# brainslug_34drc.net
KiCad netlist of a schematic drawn in EAGLE
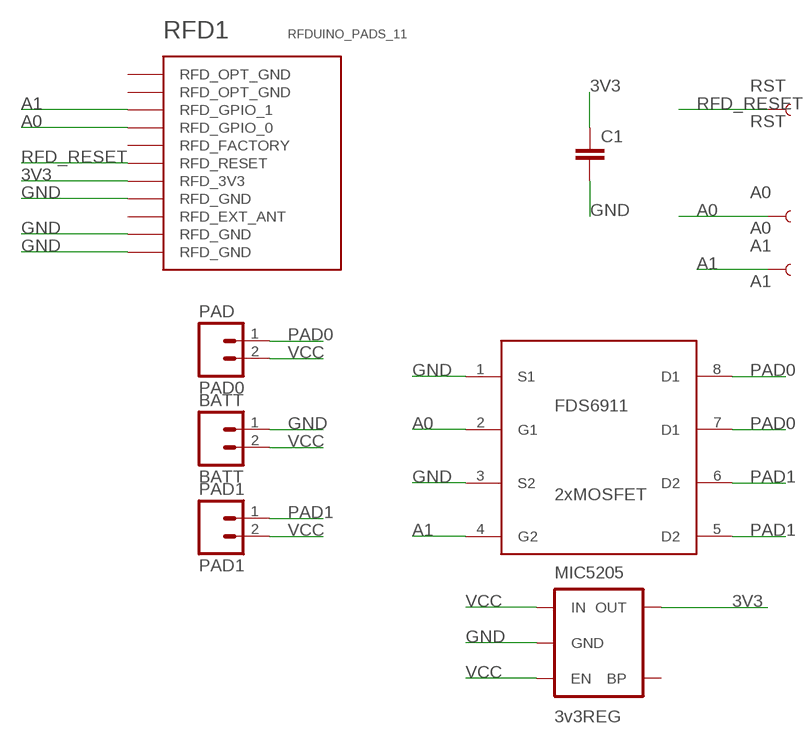
[diagram p0: schematic, sheet 1]

(export (version "E")
  (design (tool "Eeschema 10.0.6"))
  (components
    (comp (ref "A0")
      (value "A0")
      (footprint "eagle-import:PAD.03X.03")
      (libsource (lib "eagle-import") (part "TEST-POINT3"))
    )
    (comp (ref "A1")
      (value "A1")
      (footprint "eagle-import:PAD.03X.03")
      (libsource (lib "eagle-import") (part "TEST-POINT3"))
    )
    (comp (ref "BATT")
      (value "BATT")
      (footprint "eagle-import:JST-2-SMD")
      (libsource (lib "eagle-import") (part "M02-JST-2MM-SMT"))
    )
    (comp (ref "C1")
      (value "CAP")
      (footprint "eagle-import:C3216")
      (libsource (lib "eagle-import") (part "CAP"))
    )
    (comp (ref "FDS6911")
      (value "2xMOSFET")
      (footprint "eagle-import:SO8")
      (libsource (lib "eagle-import") (part "FDS6911"))
    )
    (comp (ref "MIC5205")
      (value "3v3REG")
      (footprint "eagle-import:SOT23-5")
      (libsource (lib "eagle-import") (part "MIC52053.3V"))
    )
    (comp (ref "PAD")
      (value "PAD0")
      (footprint "eagle-import:JST-2-SMD")
      (libsource (lib "eagle-import") (part "M02-JST-2MM-SMT"))
    )
    (comp (ref "PAD1")
      (value "PAD1")
      (footprint "eagle-import:JST-2-SMD")
      (libsource (lib "eagle-import") (part "M02-JST-2MM-SMT"))
    )
    (comp (ref "RFD1")
      (value "RFDUINO_PADS_11")
      (footprint "eagle-import:RFDUINO_PADS")
      (libsource (lib "eagle-import") (part "RFDUINO_PADS_11"))
    )
    (comp (ref "RST")
      (value "RST")
      (footprint "eagle-import:PAD.03X.03")
      (libsource (lib "eagle-import") (part "TEST-POINT3"))
    )
  )
  (nets
    (net (code "1") (name "/3V3") (class "Default")
      (node (ref "C1") (pin "1") (pinfunction "1_1") (pintype "passive"))
      (node (ref "MIC5205") (pin "5") (pinfunction "OUT_5") (pintype "passive"))
      (node (ref "RFD1") (pin "RFD_3V3") (pinfunction "RFD_3V3_RFD_3V3") (pintype "power_in"))
    )
    (net (code "2") (name "/A0") (class "Default")
      (node (ref "A0") (pin "P$1") (pinfunction "1_P$1") (pintype "bidirectional"))
      (node (ref "FDS6911") (pin "2") (pinfunction "G1_2") (pintype "bidirectional"))
      (node (ref "RFD1") (pin "RFD_GPIO_0") (pinfunction "RFD_GPIO_0_RFD_GPIO_0") (pintype "bidirectional"))
    )
    (net (code "3") (name "/A1") (class "Default")
      (node (ref "A1") (pin "P$1") (pinfunction "1_P$1") (pintype "bidirectional"))
      (node (ref "FDS6911") (pin "4") (pinfunction "G2_4") (pintype "bidirectional"))
      (node (ref "RFD1") (pin "RFD_GPIO_1") (pinfunction "RFD_GPIO_1_RFD_GPIO_1") (pintype "bidirectional"))
    )
    (net (code "4") (name "/GND") (class "Default")
      (node (ref "BATT") (pin "1") (pinfunction "2_1") (pintype "passive"))
      (node (ref "C1") (pin "2") (pinfunction "2_2") (pintype "passive"))
      (node (ref "FDS6911") (pin "1") (pinfunction "S1_1") (pintype "bidirectional"))
      (node (ref "FDS6911") (pin "3") (pinfunction "S2_3") (pintype "bidirectional"))
      (node (ref "MIC5205") (pin "2") (pinfunction "GND_2") (pintype "input"))
      (node (ref "RFD1") (pin "RFD_GND@0") (pinfunction "RFD_GND_RFD_GND@0") (pintype "passive"))
      (node (ref "RFD1") (pin "RFD_GND@1") (pinfunction "RFD_GND_RFD_GND@1") (pintype "power_in"))
      (node (ref "RFD1") (pin "RFD_GND@2") (pinfunction "RFD_GND_RFD_GND@2") (pintype "power_in"))
    )
    (net (code "5") (name "/PAD0") (class "Default")
      (node (ref "FDS6911") (pin "7") (pinfunction "D1_7") (pintype "bidirectional"))
      (node (ref "FDS6911") (pin "8") (pinfunction "D1_8") (pintype "bidirectional"))
      (node (ref "PAD") (pin "1") (pinfunction "2_1") (pintype "passive"))
    )
    (net (code "6") (name "/PAD1") (class "Default")
      (node (ref "FDS6911") (pin "5") (pinfunction "D2_5") (pintype "bidirectional"))
      (node (ref "FDS6911") (pin "6") (pinfunction "D2_6") (pintype "bidirectional"))
      (node (ref "PAD1") (pin "1") (pinfunction "2_1") (pintype "passive"))
    )
    (net (code "7") (name "/RFD_RESET") (class "Default")
      (node (ref "RFD1") (pin "RFD_RESET") (pinfunction "RFD_RESET_RFD_RESET") (pintype "input"))
      (node (ref "RST") (pin "P$1") (pinfunction "1_P$1") (pintype "bidirectional"))
    )
    (net (code "8") (name "/VCC") (class "Default")
      (node (ref "BATT") (pin "2") (pinfunction "1_2") (pintype "passive"))
      (node (ref "MIC5205") (pin "1") (pinfunction "IN_1") (pintype "input"))
      (node (ref "MIC5205") (pin "3") (pinfunction "EN_3") (pintype "input"))
      (node (ref "PAD") (pin "2") (pinfunction "1_2") (pintype "passive"))
      (node (ref "PAD1") (pin "2") (pinfunction "1_2") (pintype "passive"))
    )
    (net (code "9") (name "unconnected-(MIC5205-BP-Pad4)") (class "Default")
      (node (ref "MIC5205") (pin "4") (pinfunction "BP_4") (pintype "input"))
    )
    (net (code "10") (name "unconnected-(RFD1-PadRFD_EXT_ANT)") (class "Default")
      (node (ref "RFD1") (pin "RFD_EXT_ANT") (pinfunction "RFD_EXT_ANT_RFD_EXT_ANT") (pintype "no_connect"))
    )
    (net (code "11") (name "unconnected-(RFD1-PadRFD_FACTORY)") (class "Default")
      (node (ref "RFD1") (pin "RFD_FACTORY") (pinfunction "RFD_FACTORY_RFD_FACTORY") (pintype "no_connect"))
    )
    (net (code "12") (name "unconnected-(RFD1-RFD_OPT_GND-PadRFD_OPT_GND@0)") (class "Default")
      (node (ref "RFD1") (pin "RFD_OPT_GND@0") (pinfunction "RFD_OPT_GND_RFD_OPT_GND@0") (pintype "no_connect"))
    )
    (net (code "13") (name "unconnected-(RFD1-RFD_OPT_GND-PadRFD_OPT_GND@1)") (class "Default")
      (node (ref "RFD1") (pin "RFD_OPT_GND@1") (pinfunction "RFD_OPT_GND_RFD_OPT_GND@1") (pintype "no_connect"))
    )
  )
)
